# MCU.net
KiCad netlist of a schematic drawn in Altium Designer
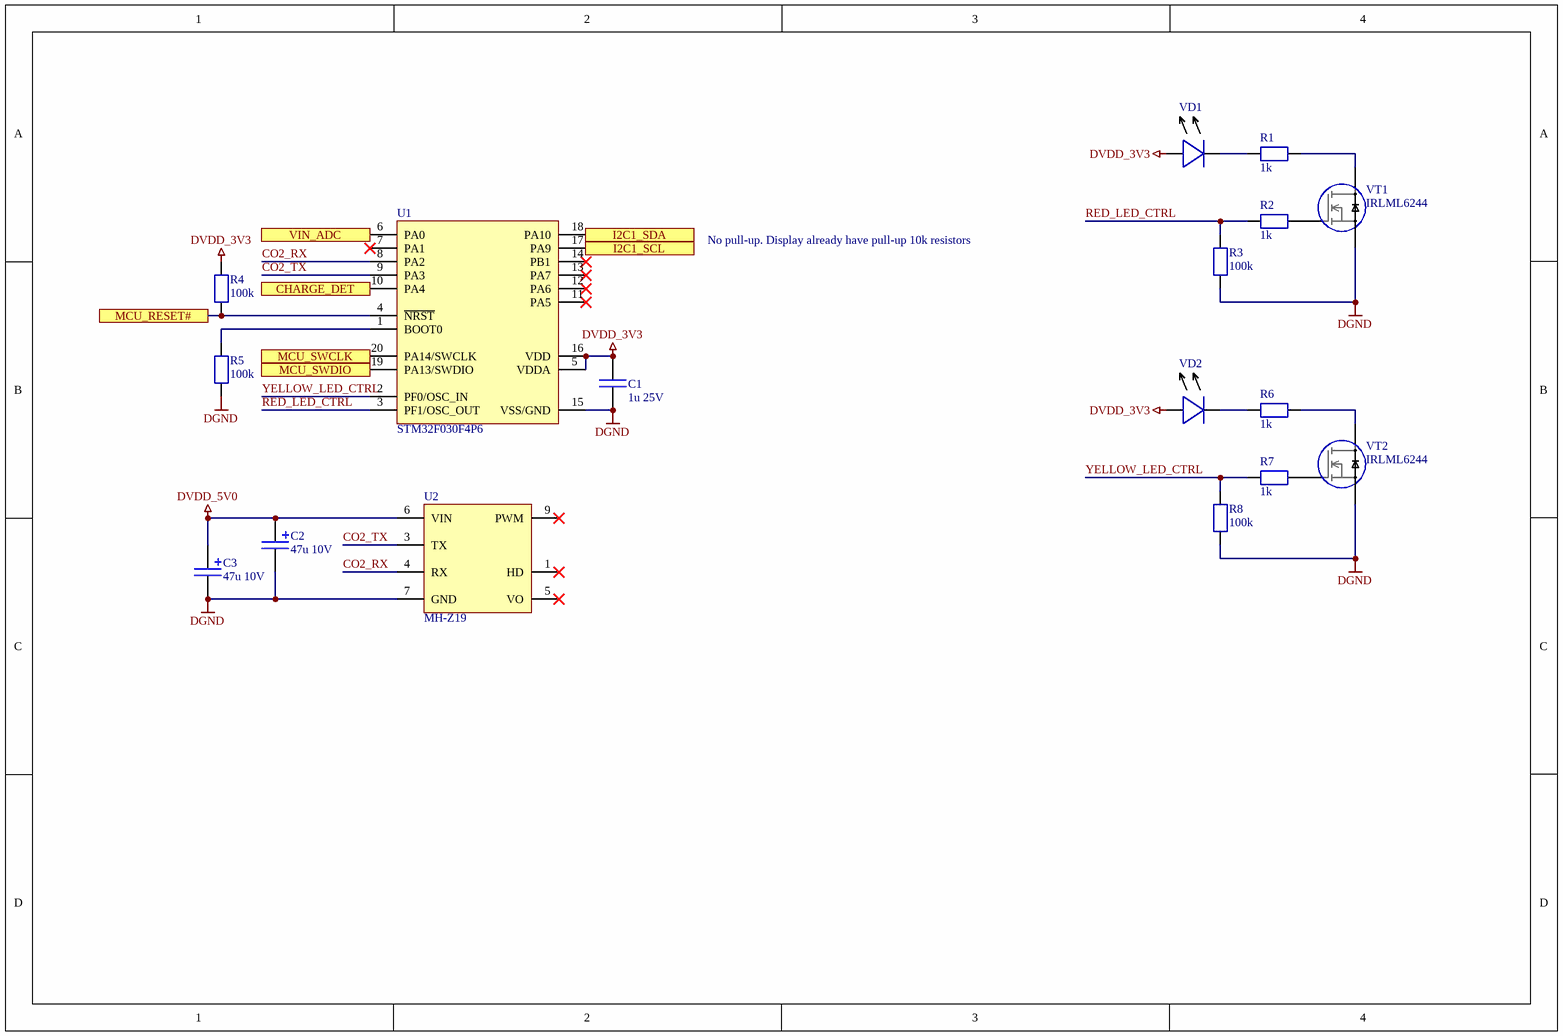
[diagram p0: MCU.SchDoc]

(export (version "E")
  (design (tool "Eeschema 10.0.6"))
  (components
    (comp (ref "C1")
      (value "1u 25V")
      (footprint "C_0603/1608")
      (description "Non-polarized capacitor")
      (libsource (lib "passive") (part "Capacitor"))
    )
    (comp (ref "C2")
      (value "47u 10V")
      (footprint "TECAP_TYPE_B")
      (description "Polarized capacitor")
      (libsource (lib "passive") (part "Capacitor polar"))
    )
    (comp (ref "C3")
      (value "47u 10V")
      (footprint "TECAP_TYPE_B")
      (description "Polarized capacitor")
      (libsource (lib "passive") (part "Capacitor polar"))
    )
    (comp (ref "R1")
      (value "1k")
      (footprint "R_0603/1608")
      (description "Resistor")
      (libsource (lib "passive") (part "Resistor"))
    )
    (comp (ref "R2")
      (value "1k")
      (footprint "R_0603/1608")
      (description "Resistor")
      (libsource (lib "passive") (part "Resistor"))
    )
    (comp (ref "R3")
      (value "100k")
      (footprint "R_0603/1608")
      (description "Resistor")
      (libsource (lib "passive") (part "Resistor"))
    )
    (comp (ref "R4")
      (value "100k")
      (footprint "R_0603/1608")
      (description "Resistor")
      (libsource (lib "passive") (part "Resistor"))
    )
    (comp (ref "R5")
      (value "100k")
      (footprint "R_0603/1608")
      (description "Resistor")
      (libsource (lib "passive") (part "Resistor"))
    )
    (comp (ref "R6")
      (value "1k")
      (footprint "R_0603/1608")
      (description "Resistor")
      (libsource (lib "passive") (part "Resistor"))
    )
    (comp (ref "R7")
      (value "1k")
      (footprint "R_0603/1608")
      (description "Resistor")
      (libsource (lib "passive") (part "Resistor"))
    )
    (comp (ref "R8")
      (value "100k")
      (footprint "R_0603/1608")
      (description "Resistor")
      (libsource (lib "passive") (part "Resistor"))
    )
    (comp (ref "U1")
      (value "STM32F030F4P6")
      (footprint "SO20_0.65")
      (description "32-bit Cortex-M0")
      (libsource (lib "MCU and memory") (part "STM32F030F"))
    )
    (comp (ref "U2")
      (value "MH-Z19")
      (footprint "MH-Z19")
      (description "CO2 sensor")
      (libsource (lib "devices") (part "MH-Z19"))
    )
    (comp (ref "VD1")
      (value "~")
      (footprint "PLS-2 2.54")
      (description "LED")
      (libsource (lib "indication") (part "LED"))
    )
    (comp (ref "VD2")
      (value "~")
      (footprint "PLS-2 2.54")
      (description "LED")
      (libsource (lib "indication") (part "LED"))
    )
    (comp (ref "VT1")
      (value "IRLML6244")
      (footprint "SOT23-3")
      (description "MOSFET N")
      (libsource (lib "active") (part "MOSFET N"))
    )
    (comp (ref "VT2")
      (value "IRLML6244")
      (footprint "SOT23-3")
      (description "MOSFET N")
      (libsource (lib "active") (part "MOSFET N"))
    )
  )
  (nets
    (net (code "1") (name "/CHARGE_DET") (class "Default")
      (node (ref "U1") (pin "10") (pinfunction "PA4_10") (pintype "passive"))
    )
    (net (code "2") (name "/CO2_RX") (class "Default")
      (node (ref "U1") (pin "8") (pinfunction "PA2_8") (pintype "passive"))
      (node (ref "U2") (pin "4") (pinfunction "RX_4") (pintype "passive"))
    )
    (net (code "3") (name "/CO2_TX") (class "Default")
      (node (ref "U1") (pin "9") (pinfunction "PA3_9") (pintype "passive"))
      (node (ref "U2") (pin "3") (pinfunction "TX_3") (pintype "passive"))
    )
    (net (code "4") (name "/I2C1_SCL") (class "Default")
      (node (ref "U1") (pin "17") (pinfunction "PA9_17") (pintype "passive"))
    )
    (net (code "5") (name "/I2C1_SDA") (class "Default")
      (node (ref "U1") (pin "18") (pinfunction "PA10_18") (pintype "passive"))
    )
    (net (code "6") (name "/MCU_RESET#") (class "Default")
      (node (ref "R4") (pin "2") (pintype "passive"))
      (node (ref "U1") (pin "4") (pinfunction "~{NRST}_4") (pintype "passive"))
    )
    (net (code "7") (name "/MCU_SWCLK") (class "Default")
      (node (ref "U1") (pin "20") (pinfunction "PA14/SWCLK_20") (pintype "passive"))
    )
    (net (code "8") (name "/MCU_SWDIO") (class "Default")
      (node (ref "U1") (pin "19") (pinfunction "PA13/SWDIO_19") (pintype "passive"))
    )
    (net (code "9") (name "/RED_LED_CTRL") (class "Default")
      (node (ref "R2") (pin "2") (pintype "passive"))
      (node (ref "R3") (pin "2") (pintype "passive"))
      (node (ref "U1") (pin "3") (pinfunction "PF1/OSC_OUT_3") (pintype "passive"))
    )
    (net (code "10") (name "/VIN_ADC") (class "Default")
      (node (ref "U1") (pin "6") (pinfunction "PA0_6") (pintype "passive"))
    )
    (net (code "11") (name "/YELLOW_LED_CTRL") (class "Default")
      (node (ref "R7") (pin "2") (pintype "passive"))
      (node (ref "R8") (pin "2") (pintype "passive"))
      (node (ref "U1") (pin "2") (pinfunction "PF0/OSC_IN_2") (pintype "passive"))
    )
    (net (code "12") (name "DGND") (class "Default")
      (node (ref "C1") (pin "2") (pintype "passive"))
      (node (ref "C2") (pin "2") (pinfunction "NEG_2") (pintype "passive"))
      (node (ref "C3") (pin "2") (pinfunction "NEG_2") (pintype "passive"))
      (node (ref "R3") (pin "1") (pintype "passive"))
      (node (ref "R5") (pin "1") (pintype "passive"))
      (node (ref "R8") (pin "1") (pintype "passive"))
      (node (ref "U1") (pin "15") (pinfunction "VSS/GND_15") (pintype "passive"))
      (node (ref "U2") (pin "7") (pinfunction "GND_7") (pintype "passive"))
      (node (ref "VT1") (pin "S") (pintype "passive"))
      (node (ref "VT2") (pin "S") (pintype "passive"))
    )
    (net (code "13") (name "DVDD_3V3") (class "Default")
      (node (ref "C1") (pin "1") (pintype "passive"))
      (node (ref "R4") (pin "1") (pintype "passive"))
      (node (ref "U1") (pin "16") (pinfunction "VDD_16") (pintype "passive"))
      (node (ref "U1") (pin "5") (pinfunction "VDDA_5") (pintype "passive"))
      (node (ref "VD1") (pin "A") (pinfunction "A_A") (pintype "passive"))
      (node (ref "VD2") (pin "A") (pinfunction "A_A") (pintype "passive"))
    )
    (net (code "14") (name "DVDD_5V0") (class "Default")
      (node (ref "C2") (pin "1") (pinfunction "POS_1") (pintype "passive"))
      (node (ref "C3") (pin "1") (pinfunction "POS_1") (pintype "passive"))
      (node (ref "U2") (pin "6") (pinfunction "VIN_6") (pintype "passive"))
    )
    (net (code "15") (name "Net-(R1-Pad1)") (class "Default")
      (node (ref "R1") (pin "1") (pintype "passive"))
      (node (ref "VT1") (pin "D") (pintype "passive"))
    )
    (net (code "16") (name "Net-(R1-Pad2)") (class "Default")
      (node (ref "R1") (pin "2") (pintype "passive"))
      (node (ref "VD1") (pin "C") (pinfunction "C_C") (pintype "passive"))
    )
    (net (code "17") (name "Net-(R2-Pad1)") (class "Default")
      (node (ref "R2") (pin "1") (pintype "passive"))
      (node (ref "VT1") (pin "G") (pintype "passive"))
    )
    (net (code "18") (name "Net-(R6-Pad1)") (class "Default")
      (node (ref "R6") (pin "1") (pintype "passive"))
      (node (ref "VT2") (pin "D") (pintype "passive"))
    )
    (net (code "19") (name "Net-(R6-Pad2)") (class "Default")
      (node (ref "R6") (pin "2") (pintype "passive"))
      (node (ref "VD2") (pin "C") (pinfunction "C_C") (pintype "passive"))
    )
    (net (code "20") (name "Net-(R7-Pad1)") (class "Default")
      (node (ref "R7") (pin "1") (pintype "passive"))
      (node (ref "VT2") (pin "G") (pintype "passive"))
    )
    (net (code "21") (name "Net-(U1-BOOT0)") (class "Default")
      (node (ref "R5") (pin "2") (pintype "passive"))
      (node (ref "U1") (pin "1") (pinfunction "BOOT0_1") (pintype "passive"))
    )
    (net (code "22") (name "unconnected-(U1-EP-Pad0)") (class "Default")
      (node (ref "U1") (pin "0") (pinfunction "EP_0") (pintype "passive"))
    )
    (net (code "23") (name "unconnected-(U1-PA1-Pad7)") (class "Default")
      (node (ref "U1") (pin "7") (pinfunction "PA1_7") (pintype "passive+no_connect"))
    )
    (net (code "24") (name "unconnected-(U1-PA5-Pad11)") (class "Default")
      (node (ref "U1") (pin "11") (pinfunction "PA5_11") (pintype "passive+no_connect"))
    )
    (net (code "25") (name "unconnected-(U1-PA6-Pad12)") (class "Default")
      (node (ref "U1") (pin "12") (pinfunction "PA6_12") (pintype "passive+no_connect"))
    )
    (net (code "26") (name "unconnected-(U1-PA7-Pad13)") (class "Default")
      (node (ref "U1") (pin "13") (pinfunction "PA7_13") (pintype "passive+no_connect"))
    )
    (net (code "27") (name "unconnected-(U1-PB1-Pad14)") (class "Default")
      (node (ref "U1") (pin "14") (pinfunction "PB1_14") (pintype "passive+no_connect"))
    )
    (net (code "28") (name "unconnected-(U2-EP-Pad0)") (class "Default")
      (node (ref "U2") (pin "0") (pinfunction "EP_0") (pintype "passive"))
    )
    (net (code "29") (name "unconnected-(U2-HD-Pad1)") (class "Default")
      (node (ref "U2") (pin "1") (pinfunction "HD_1") (pintype "passive+no_connect"))
    )
    (net (code "30") (name "unconnected-(U2-PWM-Pad9)") (class "Default")
      (node (ref "U2") (pin "9") (pinfunction "PWM_9") (pintype "passive+no_connect"))
    )
    (net (code "31") (name "unconnected-(U2-VO-Pad5)") (class "Default")
      (node (ref "U2") (pin "5") (pinfunction "VO_5") (pintype "passive+no_connect"))
    )
  )
)
